# Amplifiers1.net
KiCad netlist of a schematic drawn in Altium Designer
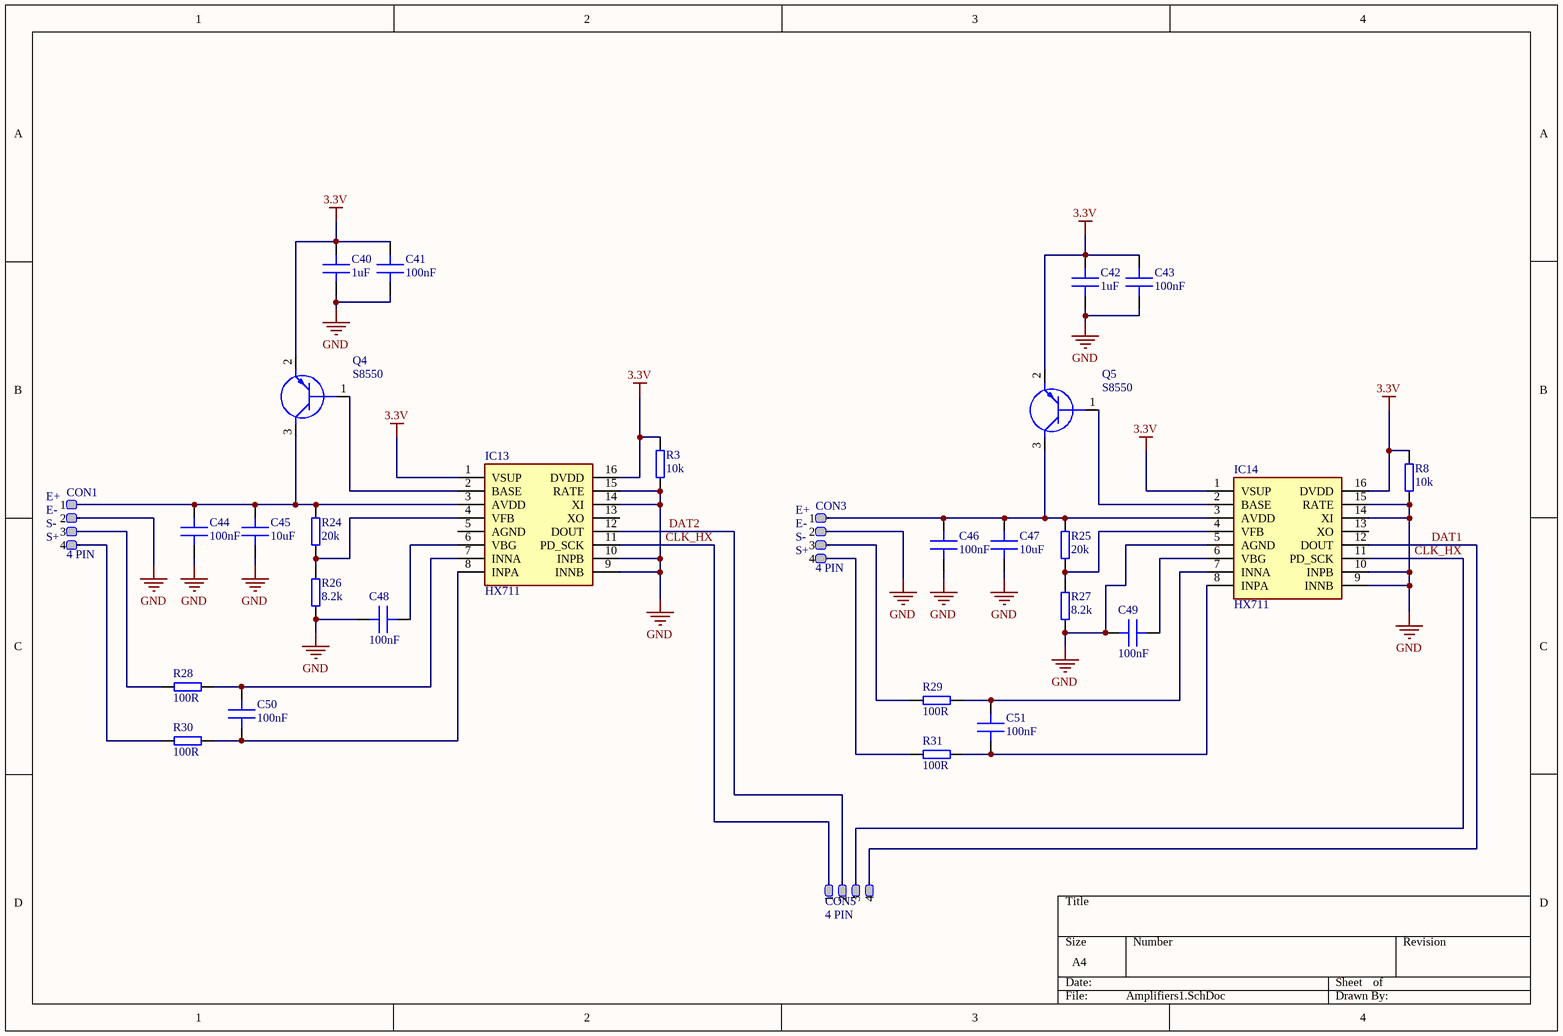
[diagram p0: Amplifiers1.SchDoc]

(export (version "E")
  (design (tool "Eeschema 10.0.6"))
  (components
    (comp (ref "C40")
      (value "1uF")
      (footprint "C 0402")
      (description "MLCC Capacitor")
      (libsource (lib "Components") (part "Capacitor"))
    )
    (comp (ref "C41")
      (value "100nF")
      (footprint "C 0402")
      (description "MLCC Capacitor")
      (libsource (lib "Components") (part "Capacitor"))
    )
    (comp (ref "C42")
      (value "1uF")
      (footprint "C 0402")
      (description "MLCC Capacitor")
      (libsource (lib "Components") (part "Capacitor"))
    )
    (comp (ref "C43")
      (value "100nF")
      (footprint "C 0402")
      (description "MLCC Capacitor")
      (libsource (lib "Components") (part "Capacitor"))
    )
    (comp (ref "C44")
      (value "100nF")
      (footprint "C 0402")
      (description "MLCC Capacitor")
      (libsource (lib "Components") (part "Capacitor"))
    )
    (comp (ref "C45")
      (value "10uF")
      (footprint "C 0402")
      (description "MLCC Capacitor")
      (libsource (lib "Components") (part "Capacitor"))
    )
    (comp (ref "C46")
      (value "100nF")
      (footprint "C 0402")
      (description "MLCC Capacitor")
      (libsource (lib "Components") (part "Capacitor"))
    )
    (comp (ref "C47")
      (value "10uF")
      (footprint "C 0402")
      (description "MLCC Capacitor")
      (libsource (lib "Components") (part "Capacitor"))
    )
    (comp (ref "C48")
      (value "100nF")
      (footprint "C 0402")
      (description "MLCC Capacitor")
      (libsource (lib "Components") (part "Capacitor"))
    )
    (comp (ref "C49")
      (value "100nF")
      (footprint "C 0402")
      (description "MLCC Capacitor")
      (libsource (lib "Components") (part "Capacitor"))
    )
    (comp (ref "C50")
      (value "100nF")
      (footprint "C 0402")
      (description "MLCC Capacitor")
      (libsource (lib "Components") (part "Capacitor"))
    )
    (comp (ref "C51")
      (value "100nF")
      (footprint "C 0402")
      (description "MLCC Capacitor")
      (libsource (lib "Components") (part "Capacitor"))
    )
    (comp (ref "CON1")
      (value "4 PIN")
      (footprint "BM04B-SRSS-TB")
      (libsource (lib "Connectors") (part "4 PIN"))
    )
    (comp (ref "CON3")
      (value "4 PIN")
      (footprint "BM04B-SRSS-TB")
      (libsource (lib "Connectors") (part "4 PIN"))
    )
    (comp (ref "CON5")
      (value "4 PIN")
      (footprint "Goldpin 1.27mm 4PIN")
      (libsource (lib "Connectors") (part "4 PIN"))
    )
    (comp (ref "IC13")
      (value "HX711")
      (footprint "SamacSys:SOIC127P600X160-16N")
      (description "Integrated Circuit")
      (libsource (lib "caravan_sch_lib") (part "HX711"))
    )
    (comp (ref "IC14")
      (value "HX711")
      (footprint "SamacSys:SOIC127P600X160-16N")
      (description "Integrated Circuit")
      (libsource (lib "caravan_sch_lib") (part "HX711"))
    )
    (comp (ref "Q4")
      (value "S8550")
      (footprint "SamacSys:SOT95P240X110-3N")
      (description "Transistor BJT PNP")
      (libsource (lib "*") (part "S8550"))
    )
    (comp (ref "Q5")
      (value "S8550")
      (footprint "SamacSys:SOT95P240X110-3N")
      (description "Transistor BJT PNP")
      (libsource (lib "*") (part "S8550"))
    )
    (comp (ref "R3")
      (value "10k")
      (footprint "R 0402")
      (description "General pourpouse resistor")
      (libsource (lib "Components") (part "Resistor"))
    )
    (comp (ref "R8")
      (value "10k")
      (footprint "R 0402")
      (description "General pourpouse resistor")
      (libsource (lib "Components") (part "Resistor"))
    )
    (comp (ref "R24")
      (value "20k")
      (footprint "R 0402")
      (description "General pourpouse resistor")
      (libsource (lib "Components") (part "Resistor"))
    )
    (comp (ref "R25")
      (value "20k")
      (footprint "R 0402")
      (description "General pourpouse resistor")
      (libsource (lib "Components") (part "Resistor"))
    )
    (comp (ref "R26")
      (value "8.2k")
      (footprint "R 0402")
      (description "General pourpouse resistor")
      (libsource (lib "Components") (part "Resistor"))
    )
    (comp (ref "R27")
      (value "8.2k")
      (footprint "R 0402")
      (description "General pourpouse resistor")
      (libsource (lib "Components") (part "Resistor"))
    )
    (comp (ref "R28")
      (value "100R")
      (footprint "R 0402")
      (description "General pourpouse resistor")
      (libsource (lib "Components") (part "Resistor"))
    )
    (comp (ref "R29")
      (value "100R")
      (footprint "R 0402")
      (description "General pourpouse resistor")
      (libsource (lib "Components") (part "Resistor"))
    )
    (comp (ref "R30")
      (value "100R")
      (footprint "R 0402")
      (description "General pourpouse resistor")
      (libsource (lib "Components") (part "Resistor"))
    )
    (comp (ref "R31")
      (value "100R")
      (footprint "R 0402")
      (description "General pourpouse resistor")
      (libsource (lib "Components") (part "Resistor"))
    )
  )
  (nets
    (net (code "1") (name "/CLK_HX") (class "Default")
      (node (ref "CON5") (pin "1") (pinfunction "1_1") (pintype "passive"))
      (node (ref "CON5") (pin "3") (pinfunction "3_3") (pintype "passive"))
      (node (ref "IC13") (pin "11") (pinfunction "PD_SCK_11") (pintype "passive"))
      (node (ref "IC14") (pin "11") (pinfunction "PD_SCK_11") (pintype "passive"))
    )
    (net (code "2") (name "/DAT1") (class "Default")
      (node (ref "CON5") (pin "4") (pinfunction "4_4") (pintype "passive"))
      (node (ref "IC14") (pin "12") (pinfunction "DOUT_12") (pintype "passive"))
    )
    (net (code "3") (name "/DAT2") (class "Default")
      (node (ref "CON5") (pin "2") (pinfunction "2_2") (pintype "passive"))
      (node (ref "IC13") (pin "12") (pinfunction "DOUT_12") (pintype "passive"))
    )
    (net (code "4") (name "3.3V") (class "Default")
      (node (ref "C40") (pin "1") (pinfunction "1_1") (pintype "passive"))
      (node (ref "C41") (pin "1") (pinfunction "1_1") (pintype "passive"))
      (node (ref "C42") (pin "1") (pinfunction "1_1") (pintype "passive"))
      (node (ref "C43") (pin "1") (pinfunction "1_1") (pintype "passive"))
      (node (ref "IC13") (pin "1") (pinfunction "VSUP_1") (pintype "passive"))
      (node (ref "IC13") (pin "16") (pinfunction "DVDD_16") (pintype "passive"))
      (node (ref "IC14") (pin "1") (pinfunction "VSUP_1") (pintype "passive"))
      (node (ref "IC14") (pin "16") (pinfunction "DVDD_16") (pintype "passive"))
      (node (ref "Q4") (pin "2") (pinfunction "E_2") (pintype "passive"))
      (node (ref "Q5") (pin "2") (pinfunction "E_2") (pintype "passive"))
      (node (ref "R3") (pin "2") (pinfunction "2_2") (pintype "passive"))
      (node (ref "R8") (pin "2") (pinfunction "2_2") (pintype "passive"))
    )
    (net (code "5") (name "GND") (class "Default")
      (node (ref "C40") (pin "2") (pinfunction "2_2") (pintype "passive"))
      (node (ref "C41") (pin "2") (pinfunction "2_2") (pintype "passive"))
      (node (ref "C42") (pin "2") (pinfunction "2_2") (pintype "passive"))
      (node (ref "C43") (pin "2") (pinfunction "2_2") (pintype "passive"))
      (node (ref "C44") (pin "2") (pinfunction "2_2") (pintype "passive"))
      (node (ref "C45") (pin "2") (pinfunction "2_2") (pintype "passive"))
      (node (ref "C46") (pin "2") (pinfunction "2_2") (pintype "passive"))
      (node (ref "C47") (pin "2") (pinfunction "2_2") (pintype "passive"))
      (node (ref "C48") (pin "1") (pinfunction "1_1") (pintype "passive"))
      (node (ref "C49") (pin "1") (pinfunction "1_1") (pintype "passive"))
      (node (ref "CON1") (pin "2") (pinfunction "2_2") (pintype "passive"))
      (node (ref "CON3") (pin "2") (pinfunction "2_2") (pintype "passive"))
      (node (ref "IC13") (pin "10") (pinfunction "INPB_10") (pintype "passive"))
      (node (ref "IC13") (pin "14") (pinfunction "XI_14") (pintype "passive"))
      (node (ref "IC13") (pin "15") (pinfunction "RATE_15") (pintype "passive"))
      (node (ref "IC13") (pin "9") (pinfunction "INNB_9") (pintype "passive"))
      (node (ref "IC14") (pin "10") (pinfunction "INPB_10") (pintype "passive"))
      (node (ref "IC14") (pin "14") (pinfunction "XI_14") (pintype "passive"))
      (node (ref "IC14") (pin "15") (pinfunction "RATE_15") (pintype "passive"))
      (node (ref "IC14") (pin "5") (pinfunction "AGND_5") (pintype "passive"))
      (node (ref "IC14") (pin "9") (pinfunction "INNB_9") (pintype "passive"))
      (node (ref "R26") (pin "1") (pinfunction "1_1") (pintype "passive"))
      (node (ref "R27") (pin "1") (pinfunction "1_1") (pintype "passive"))
      (node (ref "R3") (pin "1") (pinfunction "1_1") (pintype "passive"))
      (node (ref "R8") (pin "1") (pinfunction "1_1") (pintype "passive"))
    )
    (net (code "6") (name "Net-(CON1-Pad3)") (class "Default")
      (node (ref "CON1") (pin "3") (pinfunction "3_3") (pintype "passive"))
      (node (ref "R28") (pin "2") (pinfunction "2_2") (pintype "passive"))
    )
    (net (code "7") (name "Net-(CON1-Pad4)") (class "Default")
      (node (ref "CON1") (pin "4") (pinfunction "4_4") (pintype "passive"))
      (node (ref "R30") (pin "2") (pinfunction "2_2") (pintype "passive"))
    )
    (net (code "8") (name "Net-(CON3-Pad3)") (class "Default")
      (node (ref "CON3") (pin "3") (pinfunction "3_3") (pintype "passive"))
      (node (ref "R29") (pin "2") (pinfunction "2_2") (pintype "passive"))
    )
    (net (code "9") (name "Net-(CON3-Pad4)") (class "Default")
      (node (ref "CON3") (pin "4") (pinfunction "4_4") (pintype "passive"))
      (node (ref "R31") (pin "2") (pinfunction "2_2") (pintype "passive"))
    )
    (net (code "10") (name "Net-(IC13-AVDD)") (class "Default")
      (node (ref "C44") (pin "1") (pinfunction "1_1") (pintype "passive"))
      (node (ref "C45") (pin "1") (pinfunction "1_1") (pintype "passive"))
      (node (ref "CON1") (pin "1") (pinfunction "1_1") (pintype "passive"))
      (node (ref "IC13") (pin "3") (pinfunction "AVDD_3") (pintype "passive"))
      (node (ref "Q4") (pin "3") (pinfunction "C_3") (pintype "passive"))
      (node (ref "R24") (pin "2") (pinfunction "2_2") (pintype "passive"))
    )
    (net (code "11") (name "Net-(IC13-BASE)") (class "Default")
      (node (ref "IC13") (pin "2") (pinfunction "BASE_2") (pintype "passive"))
      (node (ref "Q4") (pin "1") (pinfunction "B_1") (pintype "passive"))
    )
    (net (code "12") (name "Net-(IC13-INNA)") (class "Default")
      (node (ref "C50") (pin "2") (pinfunction "2_2") (pintype "passive"))
      (node (ref "IC13") (pin "7") (pinfunction "INNA_7") (pintype "passive"))
      (node (ref "R28") (pin "1") (pinfunction "1_1") (pintype "passive"))
    )
    (net (code "13") (name "Net-(IC13-INPA)") (class "Default")
      (node (ref "C50") (pin "1") (pinfunction "1_1") (pintype "passive"))
      (node (ref "IC13") (pin "8") (pinfunction "INPA_8") (pintype "passive"))
      (node (ref "R30") (pin "1") (pinfunction "1_1") (pintype "passive"))
    )
    (net (code "14") (name "Net-(IC13-VBG)") (class "Default")
      (node (ref "C48") (pin "2") (pinfunction "2_2") (pintype "passive"))
      (node (ref "IC13") (pin "6") (pinfunction "VBG_6") (pintype "passive"))
    )
    (net (code "15") (name "Net-(IC13-VFB)") (class "Default")
      (node (ref "IC13") (pin "4") (pinfunction "VFB_4") (pintype "passive"))
      (node (ref "R24") (pin "1") (pinfunction "1_1") (pintype "passive"))
      (node (ref "R26") (pin "2") (pinfunction "2_2") (pintype "passive"))
    )
    (net (code "16") (name "Net-(IC14-AVDD)") (class "Default")
      (node (ref "C46") (pin "1") (pinfunction "1_1") (pintype "passive"))
      (node (ref "C47") (pin "1") (pinfunction "1_1") (pintype "passive"))
      (node (ref "CON3") (pin "1") (pinfunction "1_1") (pintype "passive"))
      (node (ref "IC14") (pin "3") (pinfunction "AVDD_3") (pintype "passive"))
      (node (ref "Q5") (pin "3") (pinfunction "C_3") (pintype "passive"))
      (node (ref "R25") (pin "2") (pinfunction "2_2") (pintype "passive"))
    )
    (net (code "17") (name "Net-(IC14-BASE)") (class "Default")
      (node (ref "IC14") (pin "2") (pinfunction "BASE_2") (pintype "passive"))
      (node (ref "Q5") (pin "1") (pinfunction "B_1") (pintype "passive"))
    )
    (net (code "18") (name "Net-(IC14-INNA)") (class "Default")
      (node (ref "C51") (pin "2") (pinfunction "2_2") (pintype "passive"))
      (node (ref "IC14") (pin "7") (pinfunction "INNA_7") (pintype "passive"))
      (node (ref "R29") (pin "1") (pinfunction "1_1") (pintype "passive"))
    )
    (net (code "19") (name "Net-(IC14-INPA)") (class "Default")
      (node (ref "C51") (pin "1") (pinfunction "1_1") (pintype "passive"))
      (node (ref "IC14") (pin "8") (pinfunction "INPA_8") (pintype "passive"))
      (node (ref "R31") (pin "1") (pinfunction "1_1") (pintype "passive"))
    )
    (net (code "20") (name "Net-(IC14-VBG)") (class "Default")
      (node (ref "C49") (pin "2") (pinfunction "2_2") (pintype "passive"))
      (node (ref "IC14") (pin "6") (pinfunction "VBG_6") (pintype "passive"))
    )
    (net (code "21") (name "Net-(IC14-VFB)") (class "Default")
      (node (ref "IC14") (pin "4") (pinfunction "VFB_4") (pintype "passive"))
      (node (ref "R25") (pin "1") (pinfunction "1_1") (pintype "passive"))
      (node (ref "R27") (pin "2") (pinfunction "2_2") (pintype "passive"))
    )
    (net (code "22") (name "unconnected-(IC13-AGND-Pad5)") (class "Default")
      (node (ref "IC13") (pin "5") (pinfunction "AGND_5") (pintype "passive"))
    )
    (net (code "23") (name "unconnected-(IC13-XO-Pad13)") (class "Default")
      (node (ref "IC13") (pin "13") (pinfunction "XO_13") (pintype "passive"))
    )
    (net (code "24") (name "unconnected-(IC14-XO-Pad13)") (class "Default")
      (node (ref "IC14") (pin "13") (pinfunction "XO_13") (pintype "passive"))
    )
  )
)
